# PLL_Power.net
KiCad netlist of a schematic drawn in Altium Designer
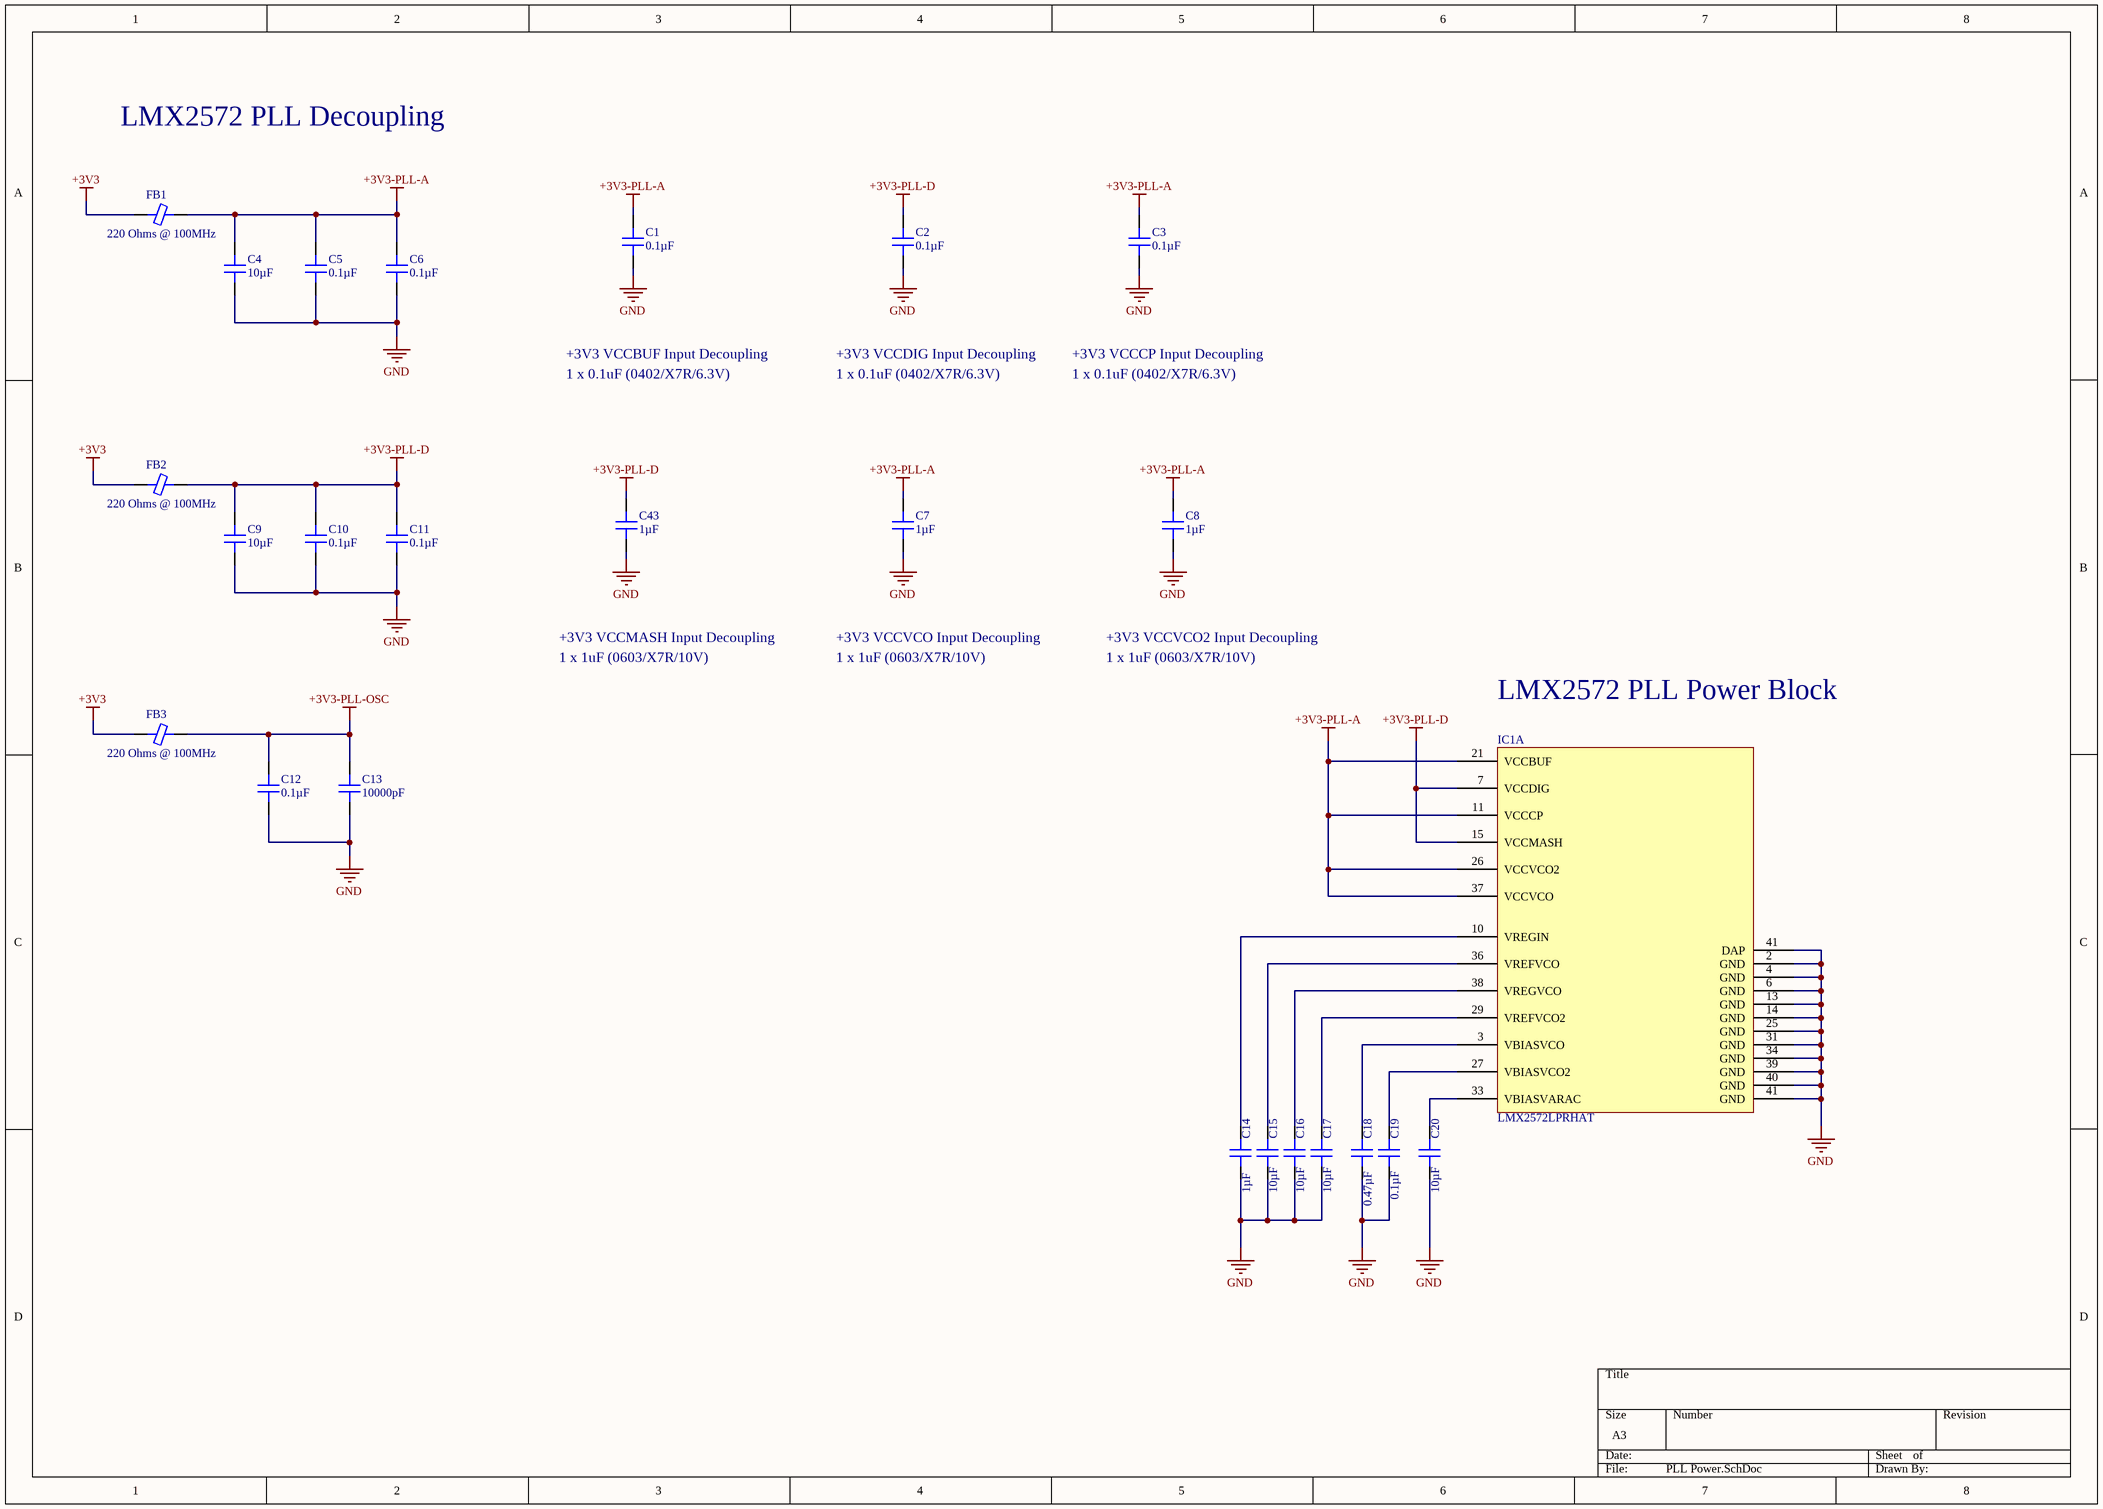
[diagram p0: PLL Power.SchDoc]

(export (version "E")
  (design (tool "Eeschema 10.0.6"))
  (components
    (comp (ref "C1")
      (value "0.1µF")
      (footprint "CAP 0402_1005")
      (description "CAP CER 0.1UF 6.3V X7R 0402")
      (fields
        (field (name "PART NUMBER") "0402B104K6R3CT")
        (field (name "MANUFACTURER") "Walsin Technology Corporation")
      )
      (libsource (lib "Generic Altium Database") (part "Capacitor"))
    )
    (comp (ref "C2")
      (value "0.1µF")
      (footprint "CAP 0402_1005")
      (description "CAP CER 0.1UF 6.3V X7R 0402")
      (fields
        (field (name "PART NUMBER") "0402B104K6R3CT")
        (field (name "MANUFACTURER") "Walsin Technology Corporation")
      )
      (libsource (lib "Generic Altium Database") (part "Capacitor"))
    )
    (comp (ref "C3")
      (value "0.1µF")
      (footprint "CAP 0402_1005")
      (description "CAP CER 0.1UF 6.3V X7R 0402")
      (fields
        (field (name "PART NUMBER") "0402B104K6R3CT")
        (field (name "MANUFACTURER") "Walsin Technology Corporation")
      )
      (libsource (lib "Generic Altium Database") (part "Capacitor"))
    )
    (comp (ref "C4")
      (value "10µF")
      (footprint "CAP 0805_2012")
      (description "CAP CER 10UF 6.3V X5R 0805")
      (fields (field (name "PART NUMBER") "08056D106KAT4A") (field (name "MANUFACTURER") "AVX Corporation"))
      (libsource (lib "Generic Altium Database") (part "Capacitor"))
    )
    (comp (ref "C5")
      (value "0.1µF")
      (footprint "CAP 0402_1005")
      (description "CAP CER 0.1UF 6.3V X7R 0402")
      (fields
        (field (name "PART NUMBER") "0402B104K6R3CT")
        (field (name "MANUFACTURER") "Walsin Technology Corporation")
      )
      (libsource (lib "Generic Altium Database") (part "Capacitor"))
    )
    (comp (ref "C6")
      (value "0.1µF")
      (footprint "CAP 0402_1005")
      (description "CAP CER 0.1UF 6.3V X7R 0402")
      (fields
        (field (name "PART NUMBER") "0402B104K6R3CT")
        (field (name "MANUFACTURER") "Walsin Technology Corporation")
      )
      (libsource (lib "Generic Altium Database") (part "Capacitor"))
    )
    (comp (ref "C7")
      (value "1µF")
      (footprint "CAP 0603_1608")
      (description "CAP CER 1UF 10V X7R 0603")
      (fields (field (name "PART NUMBER") "C0603C105K8RACTU") (field (name "MANUFACTURER") "KEMET"))
      (libsource (lib "Generic Altium Database") (part "Capacitor"))
    )
    (comp (ref "C8")
      (value "1µF")
      (footprint "CAP 0603_1608")
      (description "CAP CER 1UF 10V X7R 0603")
      (fields (field (name "PART NUMBER") "C0603C105K8RACTU") (field (name "MANUFACTURER") "KEMET"))
      (libsource (lib "Generic Altium Database") (part "Capacitor"))
    )
    (comp (ref "C9")
      (value "10µF")
      (footprint "CAP 0805_2012")
      (description "CAP CER 10UF 6.3V X5R 0805")
      (fields (field (name "PART NUMBER") "08056D106KAT4A") (field (name "MANUFACTURER") "AVX Corporation"))
      (libsource (lib "Generic Altium Database") (part "Capacitor"))
    )
    (comp (ref "C10")
      (value "0.1µF")
      (footprint "CAP 0402_1005")
      (description "CAP CER 0.1UF 6.3V X7R 0402")
      (fields
        (field (name "PART NUMBER") "0402B104K6R3CT")
        (field (name "MANUFACTURER") "Walsin Technology Corporation")
      )
      (libsource (lib "Generic Altium Database") (part "Capacitor"))
    )
    (comp (ref "C11")
      (value "0.1µF")
      (footprint "CAP 0402_1005")
      (description "CAP CER 0.1UF 6.3V X7R 0402")
      (fields
        (field (name "PART NUMBER") "0402B104K6R3CT")
        (field (name "MANUFACTURER") "Walsin Technology Corporation")
      )
      (libsource (lib "Generic Altium Database") (part "Capacitor"))
    )
    (comp (ref "C12")
      (value "0.1µF")
      (footprint "CAP 0402_1005")
      (description "CAP CER 0.1UF 6.3V X7R 0402")
      (fields
        (field (name "PART NUMBER") "0402B104K6R3CT")
        (field (name "MANUFACTURER") "Walsin Technology Corporation")
      )
      (libsource (lib "Generic Altium Database") (part "Capacitor"))
    )
    (comp (ref "C13")
      (value "10000pF")
      (footprint "CAP 0402_1005")
      (description "CAP, MLCC, 0402/1005, 16V, X7R,")
      (fields (field (name "PART NUMBER") "EMF105B7103KVHF") (field (name "MANUFACTURER") "Taiyo Yuden"))
      (libsource (lib "Generic Altium Database") (part "Capacitor"))
    )
    (comp (ref "C14")
      (value "1µF")
      (footprint "CAP 0603_1608")
      (description "CAP CER 1UF 10V X7R 0603")
      (fields (field (name "PART NUMBER") "C0603C105K8RACTU") (field (name "MANUFACTURER") "KEMET"))
      (libsource (lib "Generic Altium Database") (part "Capacitor"))
    )
    (comp (ref "C15")
      (value "10µF")
      (footprint "CAP 0805_2012")
      (description "CAP CER 10UF 6.3V X5R 0805")
      (fields (field (name "PART NUMBER") "08056D106KAT4A") (field (name "MANUFACTURER") "AVX Corporation"))
      (libsource (lib "Generic Altium Database") (part "Capacitor"))
    )
    (comp (ref "C16")
      (value "10µF")
      (footprint "CAP 0805_2012")
      (description "CAP CER 10UF 6.3V X5R 0805")
      (fields (field (name "PART NUMBER") "08056D106KAT4A") (field (name "MANUFACTURER") "AVX Corporation"))
      (libsource (lib "Generic Altium Database") (part "Capacitor"))
    )
    (comp (ref "C17")
      (value "10µF")
      (footprint "CAP 0805_2012")
      (description "CAP CER 10UF 6.3V X5R 0805")
      (fields (field (name "PART NUMBER") "08056D106KAT4A") (field (name "MANUFACTURER") "AVX Corporation"))
      (libsource (lib "Generic Altium Database") (part "Capacitor"))
    )
    (comp (ref "C18")
      (value "0.47µF")
      (footprint "CAP 0402_1005")
      (description "CAP CER 0.47UF 10V X7R 0402")
      (fields
        (field (name "PART NUMBER") "0402B474K100CT")
        (field (name "MANUFACTURER") "Walsin Technology Corporation")
      )
      (libsource (lib "Generic Altium Database") (part "Capacitor"))
    )
    (comp (ref "C19")
      (value "0.1µF")
      (footprint "CAP 0402_1005")
      (description "CAP CER 0.1UF 6.3V X7R 0402")
      (fields
        (field (name "PART NUMBER") "0402B104K6R3CT")
        (field (name "MANUFACTURER") "Walsin Technology Corporation")
      )
      (libsource (lib "Generic Altium Database") (part "Capacitor"))
    )
    (comp (ref "C20")
      (value "10µF")
      (footprint "CAP 0805_2012")
      (description "CAP CER 10UF 6.3V X5R 0805")
      (fields (field (name "PART NUMBER") "08056D106KAT4A") (field (name "MANUFACTURER") "AVX Corporation"))
      (libsource (lib "Generic Altium Database") (part "Capacitor"))
    )
    (comp (ref "C43")
      (value "1µF")
      (footprint "CAP 0603_1608")
      (description "CAP CER 1UF 10V X7R 0603")
      (fields (field (name "PART NUMBER") "C0603C105K8RACTU") (field (name "MANUFACTURER") "KEMET"))
      (libsource (lib "Generic Altium Database") (part "Capacitor"))
    )
    (comp (ref "FB1")
      (value "220 Ohms @ 100MHz")
      (footprint "FER 0402_1005")
      (description "EMI BEAD FILETER")
      (fields
        (field (name "PART NUMBER") "BBPY00100505221Y00")
        (field (name "MANUFACTURER") "Chilisin Electronics")
      )
      (libsource (lib "Generic Altium Database") (part "Ferrite Chip"))
    )
    (comp (ref "FB2")
      (value "220 Ohms @ 100MHz")
      (footprint "FER 0402_1005")
      (description "EMI BEAD FILETER")
      (fields
        (field (name "PART NUMBER") "BBPY00100505221Y00")
        (field (name "MANUFACTURER") "Chilisin Electronics")
      )
      (libsource (lib "Generic Altium Database") (part "Ferrite Chip"))
    )
    (comp (ref "FB3")
      (value "220 Ohms @ 100MHz")
      (footprint "FER 0402_1005")
      (description "EMI BEAD FILETER")
      (fields
        (field (name "PART NUMBER") "BBPY00100505221Y00")
        (field (name "MANUFACTURER") "Chilisin Electronics")
      )
      (libsource (lib "Generic Altium Database") (part "Ferrite Chip"))
    )
    (comp (ref "IC1")
      (value "LMX2572LPRHAT")
      (footprint "TI VQFN-40 6X6MM")
      (description "IC FREQUENCY SYNTH 40VQFN")
      (fields (field (name "MANUFACTURER") "Texas Instruments"))
      (libsource (lib "Generic Altium Database") (part "TI LMX2572"))
    )
  )
  (nets
    (net (code "1") (name "+3V3") (class "Default")
      (node (ref "FB1") (pin "2") (pinfunction "2_2") (pintype "passive"))
      (node (ref "FB2") (pin "2") (pinfunction "2_2") (pintype "passive"))
      (node (ref "FB3") (pin "2") (pinfunction "2_2") (pintype "passive"))
    )
    (net (code "2") (name "+3V3-PLL-A") (class "Default")
      (node (ref "C1") (pin "2") (pinfunction "2_2") (pintype "passive"))
      (node (ref "C3") (pin "2") (pinfunction "2_2") (pintype "passive"))
      (node (ref "C4") (pin "2") (pinfunction "2_2") (pintype "passive"))
      (node (ref "C5") (pin "2") (pinfunction "2_2") (pintype "passive"))
      (node (ref "C6") (pin "2") (pinfunction "2_2") (pintype "passive"))
      (node (ref "C7") (pin "1") (pinfunction "1_1") (pintype "passive"))
      (node (ref "C8") (pin "1") (pinfunction "1_1") (pintype "passive"))
      (node (ref "FB1") (pin "1") (pinfunction "1_1") (pintype "passive"))
      (node (ref "IC1") (pin "11") (pinfunction "VCCCP_11") (pintype "power_in"))
      (node (ref "IC1") (pin "21") (pinfunction "VCCBUF_21") (pintype "passive"))
      (node (ref "IC1") (pin "26") (pinfunction "VCCVCO2_26") (pintype "power_in"))
      (node (ref "IC1") (pin "37") (pinfunction "VCCVCO_37") (pintype "power_in"))
    )
    (net (code "3") (name "+3V3-PLL-D") (class "Default")
      (node (ref "C10") (pin "2") (pinfunction "2_2") (pintype "passive"))
      (node (ref "C11") (pin "2") (pinfunction "2_2") (pintype "passive"))
      (node (ref "C2") (pin "2") (pinfunction "2_2") (pintype "passive"))
      (node (ref "C43") (pin "1") (pinfunction "1_1") (pintype "passive"))
      (node (ref "C9") (pin "2") (pinfunction "2_2") (pintype "passive"))
      (node (ref "FB2") (pin "1") (pinfunction "1_1") (pintype "passive"))
      (node (ref "IC1") (pin "15") (pinfunction "VCCMASH_15") (pintype "power_in"))
      (node (ref "IC1") (pin "7") (pinfunction "VCCDIG_7") (pintype "power_in"))
    )
    (net (code "4") (name "+3V3-PLL-OSC") (class "Default")
      (node (ref "C12") (pin "2") (pinfunction "2_2") (pintype "passive"))
      (node (ref "C13") (pin "1") (pinfunction "1_1") (pintype "passive"))
      (node (ref "FB3") (pin "1") (pinfunction "1_1") (pintype "passive"))
    )
    (net (code "5") (name "GND") (class "Default")
      (node (ref "C1") (pin "1") (pinfunction "1_1") (pintype "passive"))
      (node (ref "C10") (pin "1") (pinfunction "1_1") (pintype "passive"))
      (node (ref "C11") (pin "1") (pinfunction "1_1") (pintype "passive"))
      (node (ref "C12") (pin "1") (pinfunction "1_1") (pintype "passive"))
      (node (ref "C13") (pin "2") (pinfunction "2_2") (pintype "passive"))
      (node (ref "C14") (pin "2") (pinfunction "2_2") (pintype "passive"))
      (node (ref "C15") (pin "2") (pinfunction "2_2") (pintype "passive"))
      (node (ref "C16") (pin "2") (pinfunction "2_2") (pintype "passive"))
      (node (ref "C17") (pin "2") (pinfunction "2_2") (pintype "passive"))
      (node (ref "C18") (pin "1") (pinfunction "1_1") (pintype "passive"))
      (node (ref "C19") (pin "1") (pinfunction "1_1") (pintype "passive"))
      (node (ref "C2") (pin "1") (pinfunction "1_1") (pintype "passive"))
      (node (ref "C20") (pin "2") (pinfunction "2_2") (pintype "passive"))
      (node (ref "C3") (pin "1") (pinfunction "1_1") (pintype "passive"))
      (node (ref "C4") (pin "1") (pinfunction "1_1") (pintype "passive"))
      (node (ref "C43") (pin "2") (pinfunction "2_2") (pintype "passive"))
      (node (ref "C5") (pin "1") (pinfunction "1_1") (pintype "passive"))
      (node (ref "C6") (pin "1") (pinfunction "1_1") (pintype "passive"))
      (node (ref "C7") (pin "2") (pinfunction "2_2") (pintype "passive"))
      (node (ref "C8") (pin "2") (pinfunction "2_2") (pintype "passive"))
      (node (ref "C9") (pin "1") (pinfunction "1_1") (pintype "passive"))
      (node (ref "IC1") (pin "13") (pinfunction "GND_13") (pintype "power_in"))
      (node (ref "IC1") (pin "14") (pinfunction "GND_14") (pintype "power_in"))
      (node (ref "IC1") (pin "2") (pinfunction "GND_2") (pintype "power_in"))
      (node (ref "IC1") (pin "25") (pinfunction "GND_25") (pintype "power_in"))
      (node (ref "IC1") (pin "31") (pinfunction "GND_31") (pintype "power_in"))
      (node (ref "IC1") (pin "34") (pinfunction "GND_34") (pintype "power_in"))
      (node (ref "IC1") (pin "39") (pinfunction "GND_39") (pintype "power_in"))
      (node (ref "IC1") (pin "4") (pinfunction "GND_4") (pintype "power_in"))
      (node (ref "IC1") (pin "40") (pinfunction "GND_40") (pintype "power_in"))
      (node (ref "IC1") (pin "41") (pinfunction "GND_41") (pintype "power_in"))
      (node (ref "IC1") (pin "6") (pinfunction "GND_6") (pintype "power_in"))
    )
    (net (code "6") (name "Net-(IC1A-VBIASVARAC)") (class "Default")
      (node (ref "C20") (pin "1") (pinfunction "1_1") (pintype "passive"))
      (node (ref "IC1") (pin "33") (pinfunction "VBIASVARAC_33") (pintype "power_in"))
    )
    (net (code "7") (name "Net-(IC1A-VBIASVCO)") (class "Default")
      (node (ref "C18") (pin "2") (pinfunction "2_2") (pintype "passive"))
      (node (ref "IC1") (pin "3") (pinfunction "VBIASVCO_3") (pintype "power_in"))
    )
    (net (code "8") (name "Net-(IC1A-VBIASVCO2)") (class "Default")
      (node (ref "C19") (pin "2") (pinfunction "2_2") (pintype "passive"))
      (node (ref "IC1") (pin "27") (pinfunction "VBIASVCO2_27") (pintype "power_in"))
    )
    (net (code "9") (name "Net-(IC1A-VREFVCO)") (class "Default")
      (node (ref "C15") (pin "1") (pinfunction "1_1") (pintype "passive"))
      (node (ref "IC1") (pin "36") (pinfunction "VREFVCO_36") (pintype "power_in"))
    )
    (net (code "10") (name "Net-(IC1A-VREFVCO2)") (class "Default")
      (node (ref "C17") (pin "1") (pinfunction "1_1") (pintype "passive"))
      (node (ref "IC1") (pin "29") (pinfunction "VREFVCO2_29") (pintype "power_in"))
    )
    (net (code "11") (name "Net-(IC1A-VREGIN)") (class "Default")
      (node (ref "C14") (pin "1") (pinfunction "1_1") (pintype "passive"))
      (node (ref "IC1") (pin "10") (pinfunction "VREGIN_10") (pintype "power_in"))
    )
    (net (code "12") (name "Net-(IC1A-VREGVCO)") (class "Default")
      (node (ref "C16") (pin "1") (pinfunction "1_1") (pintype "passive"))
      (node (ref "IC1") (pin "38") (pinfunction "VREGVCO_38") (pintype "power_in"))
    )
  )
)
